# Tugas1.net
KiCad netlist of a schematic drawn in Altium Designer
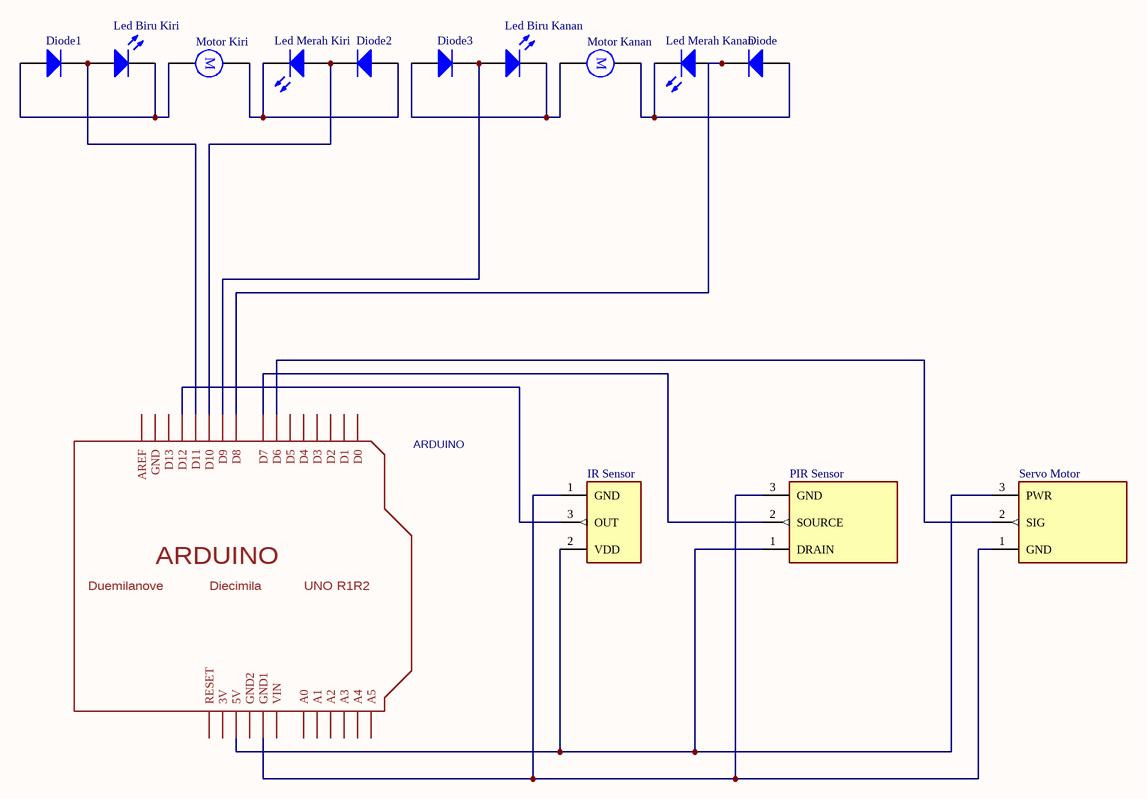
[diagram p0: Tugas1.SchDoc]

(export (version "E")
  (design (tool "Eeschema 10.0.6"))
  (components
    (comp (ref "ARDUINO")
      (value "~")
      (footprint "ARDUINO")
      (fields (field (name "CONTRIBUTOR") "Adafruit"))
      (libsource (lib "ArduinoUno") (part "ARDUINOUNO"))
    )
    (comp (ref "Diode")
      (value "~")
      (footprint "SMC")
      (description "Default Diode")
      (fields (field (name "PUBLISHER") "Altium Limited"))
      (libsource (lib "Miscellaneous Devices") (part "Diode"))
    )
    (comp (ref "Diode1")
      (value "~")
      (footprint "SMC")
      (description "Default Diode")
      (fields (field (name "PUBLISHER") "Altium Limited"))
      (libsource (lib "Miscellaneous Devices") (part "Diode"))
    )
    (comp (ref "Diode2")
      (value "~")
      (footprint "SMC")
      (description "Default Diode")
      (fields (field (name "PUBLISHER") "Altium Limited"))
      (libsource (lib "Miscellaneous Devices") (part "Diode"))
    )
    (comp (ref "Diode3")
      (value "~")
      (footprint "SMC")
      (description "Default Diode")
      (fields (field (name "PUBLISHER") "Altium Limited"))
      (libsource (lib "Miscellaneous Devices") (part "Diode"))
    )
    (comp (ref "IR Sensor")
      (value "~")
      (footprint "XDCR_TSL260R-LF")
      (description "Optical Sensor IR 940nm Voltage Radial - 3 Leads")
      (fields (field (name "MF") "ams") (field (name "MP") "TSL260R-LF"))
      (libsource (lib "TSL260R-LF") (part "TSL260R-LF"))
    )
    (comp (ref "Led Biru Kanan")
      (value "~")
      (footprint "LED-0")
      (description "Typical INFRARED GaAs LED")
      (fields (field (name "PUBLISHER") "Altium Limited"))
      (libsource (lib "Miscellaneous Devices") (part "LED0"))
    )
    (comp (ref "Led Biru Kiri")
      (value "~")
      (footprint "LED-0")
      (description "Typical INFRARED GaAs LED")
      (fields (field (name "PUBLISHER") "Altium Limited"))
      (libsource (lib "Miscellaneous Devices") (part "LED0"))
    )
    (comp (ref "Led Merah Kanan")
      (value "~")
      (footprint "LED-1")
      (description "Typical RED GaAs LED")
      (fields (field (name "PUBLISHER") "Altium Limited"))
      (libsource (lib "Miscellaneous Devices") (part "LED1"))
    )
    (comp (ref "Led Merah Kiri")
      (value "~")
      (footprint "LED-1")
      (description "Typical RED GaAs LED")
      (fields (field (name "PUBLISHER") "Altium Limited"))
      (libsource (lib "Miscellaneous Devices") (part "LED1"))
    )
    (comp (ref "Motor Kanan")
      (value "~")
      (footprint "RB5-10.5")
      (description "Motor, General Kind")
      (fields (field (name "PUBLISHER") "Altium Limited"))
      (libsource (lib "Miscellaneous Devices") (part "Motor"))
    )
    (comp (ref "Motor Kiri")
      (value "~")
      (footprint "RB5-10.5")
      (description "Motor, General Kind")
      (fields (field (name "PUBLISHER") "Altium Limited"))
      (libsource (lib "Miscellaneous Devices") (part "Motor"))
    )
    (comp (ref "PIR Sensor")
      (value "~")
      (footprint "TO254P940H490-3")
      (description "Sensor PIR _Passive Infrared_ Radial, Metal Can, Lensed - 3 Lead")
      (fields (field (name "MF") "Murata Electronics") (field (name "MP") "IRA-S210ST01"))
      (libsource (lib "IRA-S210ST01") (part "IRA-S210ST01"))
    )
    (comp (ref "Servo Motor")
      (value "~")
      (footprint "TO254P940H490-3")
      (description "Sensor PIR _Passive Infrared_ Radial, Metal Can, Lensed - 3 Lead")
      (fields (field (name "MF") "Murata Electronics") (field (name "MP") "IRA-S210ST01"))
      (libsource (lib "IRA-S210ST01") (part "IRA-S210ST01"))
    )
  )
  (nets
    (net (code "1") (name "Net-(Diode-A)") (class "Default")
      (node (ref "Diode") (pin "1") (pinfunction "A_1") (pintype "passive"))
      (node (ref "Led Merah Kanan") (pin "2") (pinfunction "K_2") (pintype "passive"))
      (node (ref "Motor Kanan") (pin "1") (pinfunction "1_1") (pintype "passive"))
    )
    (net (code "2") (name "Net-(Diode-K)") (class "Default")
      (node (ref "ARDUINO") (pin "D8") (pinfunction "D8_D8") (pintype "passive"))
      (node (ref "Diode") (pin "2") (pinfunction "K_2") (pintype "passive"))
      (node (ref "Led Merah Kanan") (pin "1") (pinfunction "A_1") (pintype "passive"))
    )
    (net (code "3") (name "Net-(Diode1-A)") (class "Default")
      (node (ref "Diode1") (pin "1") (pinfunction "A_1") (pintype "passive"))
      (node (ref "Led Biru Kiri") (pin "2") (pinfunction "K_2") (pintype "passive"))
      (node (ref "Motor Kiri") (pin "2") (pinfunction "2_2") (pintype "passive"))
    )
    (net (code "4") (name "Net-(Diode1-K)") (class "Default")
      (node (ref "ARDUINO") (pin "D11") (pinfunction "D11_D11") (pintype "passive"))
      (node (ref "Diode1") (pin "2") (pinfunction "K_2") (pintype "passive"))
      (node (ref "Led Biru Kiri") (pin "1") (pinfunction "A_1") (pintype "passive"))
    )
    (net (code "5") (name "Net-(Diode2-A)") (class "Default")
      (node (ref "Diode2") (pin "1") (pinfunction "A_1") (pintype "passive"))
      (node (ref "Led Merah Kiri") (pin "2") (pinfunction "K_2") (pintype "passive"))
      (node (ref "Motor Kiri") (pin "1") (pinfunction "1_1") (pintype "passive"))
    )
    (net (code "6") (name "Net-(Diode2-K)") (class "Default")
      (node (ref "ARDUINO") (pin "D10") (pinfunction "D10_D10") (pintype "passive"))
      (node (ref "Diode2") (pin "2") (pinfunction "K_2") (pintype "passive"))
      (node (ref "Led Merah Kiri") (pin "1") (pinfunction "A_1") (pintype "passive"))
    )
    (net (code "7") (name "Net-(Diode3-A)") (class "Default")
      (node (ref "Diode3") (pin "1") (pinfunction "A_1") (pintype "passive"))
      (node (ref "Led Biru Kanan") (pin "2") (pinfunction "K_2") (pintype "passive"))
      (node (ref "Motor Kanan") (pin "2") (pinfunction "2_2") (pintype "passive"))
    )
    (net (code "8") (name "Net-(Diode3-K)") (class "Default")
      (node (ref "ARDUINO") (pin "D9") (pinfunction "D9_D9") (pintype "passive"))
      (node (ref "Diode3") (pin "2") (pinfunction "K_2") (pintype "passive"))
      (node (ref "Led Biru Kanan") (pin "1") (pinfunction "A_1") (pintype "passive"))
    )
    (net (code "9") (name "Net-(IR Sensor-GND)") (class "Default")
      (node (ref "ARDUINO") (pin "GND1") (pinfunction "GND1_GND1") (pintype "passive"))
      (node (ref "IR Sensor") (pin "1") (pinfunction "GND_1") (pintype "power_in"))
      (node (ref "PIR Sensor") (pin "3") (pinfunction "PWR_3") (pintype "power_in"))
      (node (ref "Servo Motor") (pin "1") (pinfunction "GND_1") (pintype "power_in"))
    )
    (net (code "10") (name "Net-(IR Sensor-OUT)") (class "Default")
      (node (ref "ARDUINO") (pin "D12") (pinfunction "D12_D12") (pintype "passive"))
      (node (ref "IR Sensor") (pin "3") (pinfunction "OUT_3") (pintype "output"))
    )
    (net (code "11") (name "Net-(IR Sensor-VDD)") (class "Default")
      (node (ref "ARDUINO") (pin "5V") (pinfunction "5V_5V") (pintype "passive"))
      (node (ref "IR Sensor") (pin "2") (pinfunction "VDD_2") (pintype "power_in"))
      (node (ref "PIR Sensor") (pin "1") (pinfunction "GND_1") (pintype "power_in"))
      (node (ref "Servo Motor") (pin "3") (pinfunction "PWR_3") (pintype "power_in"))
    )
    (net (code "12") (name "Net-(PIR Sensor-SIG)") (class "Default")
      (node (ref "ARDUINO") (pin "D7") (pinfunction "D7_D7") (pintype "passive"))
      (node (ref "PIR Sensor") (pin "2") (pinfunction "SIG_2") (pintype "output"))
    )
    (net (code "13") (name "Net-(Servo Motor-SIG)") (class "Default")
      (node (ref "ARDUINO") (pin "D6") (pinfunction "D6_D6") (pintype "passive"))
      (node (ref "Servo Motor") (pin "2") (pinfunction "SIG_2") (pintype "output"))
    )
    (net (code "14") (name "unconnected-(ARDUINO-Pad3V)") (class "Default")
      (node (ref "ARDUINO") (pin "3V") (pinfunction "3V_3V") (pintype "passive"))
    )
    (net (code "15") (name "unconnected-(ARDUINO-PadA0)") (class "Default")
      (node (ref "ARDUINO") (pin "A0") (pinfunction "A0_A0") (pintype "passive"))
    )
    (net (code "16") (name "unconnected-(ARDUINO-PadA1)") (class "Default")
      (node (ref "ARDUINO") (pin "A1") (pinfunction "A1_A1") (pintype "passive"))
    )
    (net (code "17") (name "unconnected-(ARDUINO-PadA2)") (class "Default")
      (node (ref "ARDUINO") (pin "A2") (pinfunction "A2_A2") (pintype "passive"))
    )
    (net (code "18") (name "unconnected-(ARDUINO-PadA3)") (class "Default")
      (node (ref "ARDUINO") (pin "A3") (pinfunction "A3_A3") (pintype "passive"))
    )
    (net (code "19") (name "unconnected-(ARDUINO-PadA4)") (class "Default")
      (node (ref "ARDUINO") (pin "A4") (pinfunction "A4_A4") (pintype "passive"))
    )
    (net (code "20") (name "unconnected-(ARDUINO-PadA5)") (class "Default")
      (node (ref "ARDUINO") (pin "A5") (pinfunction "A5_A5") (pintype "passive"))
    )
    (net (code "21") (name "unconnected-(ARDUINO-PadAREF)") (class "Default")
      (node (ref "ARDUINO") (pin "AREF") (pinfunction "AREF_AREF") (pintype "passive"))
    )
    (net (code "22") (name "unconnected-(ARDUINO-PadD0)") (class "Default")
      (node (ref "ARDUINO") (pin "D0") (pinfunction "D0_D0") (pintype "passive"))
    )
    (net (code "23") (name "unconnected-(ARDUINO-PadD1)") (class "Default")
      (node (ref "ARDUINO") (pin "D1") (pinfunction "D1_D1") (pintype "passive"))
    )
    (net (code "24") (name "unconnected-(ARDUINO-PadD2)") (class "Default")
      (node (ref "ARDUINO") (pin "D2") (pinfunction "D2_D2") (pintype "passive"))
    )
    (net (code "25") (name "unconnected-(ARDUINO-PadD3)") (class "Default")
      (node (ref "ARDUINO") (pin "D3") (pinfunction "D3_D3") (pintype "passive"))
    )
    (net (code "26") (name "unconnected-(ARDUINO-PadD4)") (class "Default")
      (node (ref "ARDUINO") (pin "D4") (pinfunction "D4_D4") (pintype "passive"))
    )
    (net (code "27") (name "unconnected-(ARDUINO-PadD5)") (class "Default")
      (node (ref "ARDUINO") (pin "D5") (pinfunction "D5_D5") (pintype "passive"))
    )
    (net (code "28") (name "unconnected-(ARDUINO-PadD13)") (class "Default")
      (node (ref "ARDUINO") (pin "D13") (pinfunction "D13_D13") (pintype "passive"))
    )
    (net (code "29") (name "unconnected-(ARDUINO-PadGND)") (class "Default")
      (node (ref "ARDUINO") (pin "GND") (pinfunction "GND_GND") (pintype "passive"))
    )
    (net (code "30") (name "unconnected-(ARDUINO-PadGND2)") (class "Default")
      (node (ref "ARDUINO") (pin "GND2") (pinfunction "GND2_GND2") (pintype "passive"))
    )
    (net (code "31") (name "unconnected-(ARDUINO-PadRESET)") (class "Default")
      (node (ref "ARDUINO") (pin "RESET") (pinfunction "RESET_RESET") (pintype "passive"))
    )
    (net (code "32") (name "unconnected-(ARDUINO-PadVIN)") (class "Default")
      (node (ref "ARDUINO") (pin "VIN") (pinfunction "VIN_VIN") (pintype "passive"))
    )
  )
)
